# Flash_-_S25FL216K0PMFI041.net
KiCad netlist of a schematic drawn in Altium Designer
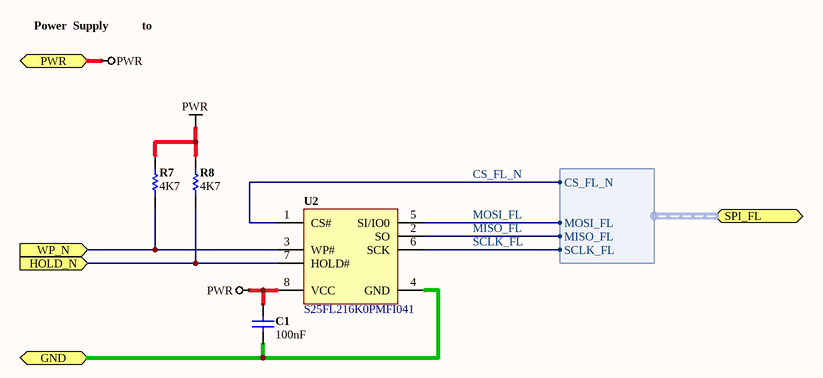
[diagram p0: Flash - S25FL216K0PMFI041.SchDoc]

(export (version "E")
  (design (tool "Eeschema 10.0.6"))
  (components
    (comp (ref "C1")
      (value "100nF")
      (footprint "CAPC0402(1005)60_L")
      (fields (field (name "TOLERANCE") "±10%") (field (name "Comment") "CAP 100nF 16V 0402(1005)"))
      (libsource (lib "Component_Database") (part "CAP_NP"))
    )
    (comp (ref "R7")
      (value "4K7")
      (footprint "RESC0402(1005)40_L")
      (fields (field (name "POWER") "1/16 W"))
      (libsource (lib "Component_Database") (part "RES"))
    )
    (comp (ref "R8")
      (value "4K7")
      (footprint "RESC0402(1005)40_L")
      (fields (field (name "POWER") "1/16 W"))
      (libsource (lib "Component_Database") (part "RES"))
    )
    (comp (ref "U2")
      (value "S25FL216K0PMFI041")
      (footprint "SPANSION-SOIC127P600X175-8M")
      (description "16-Mbit 3.0V Serial Flash Memory with Uniform 4 kB Sectors")
      (libsource (lib "S25FL216K0PMFI041") (part "S25FL216K0PMFI041"))
    )
  )
  (nets
    (net (code "2") (name "/CS_FL_N") (class "Default")
      (node (ref "U2") (pin "1") (pinfunction "CS#_1") (pintype "passive"))
    )
    (net (code "3") (name "/GND") (class "Default")
      (node (ref "C1") (pin "2") (pinfunction "2_2") (pintype "passive"))
      (node (ref "U2") (pin "4") (pinfunction "GND_4") (pintype "passive"))
    )
    (net (code "4") (name "/HOLD_N") (class "Default")
      (node (ref "R8") (pin "1") (pinfunction "1_1") (pintype "passive"))
      (node (ref "U2") (pin "7") (pinfunction "HOLD#_7") (pintype "passive"))
    )
    (net (code "5") (name "/MISO_FL") (class "Default")
      (node (ref "U2") (pin "2") (pinfunction "SO_2") (pintype "passive"))
    )
    (net (code "6") (name "/MOSI_FL") (class "Default")
      (node (ref "U2") (pin "5") (pinfunction "SI/IO0_5") (pintype "passive"))
    )
    (net (code "7") (name "/SCLK_FL") (class "Default")
      (node (ref "U2") (pin "6") (pinfunction "SCK_6") (pintype "passive"))
    )
    (net (code "8") (name "/WP_N") (class "Default")
      (node (ref "R7") (pin "1") (pinfunction "1_1") (pintype "passive"))
      (node (ref "U2") (pin "3") (pinfunction "WP#_3") (pintype "passive"))
    )
    (net (code "10") (name "PWR") (class "Default")
      (node (ref "C1") (pin "1") (pinfunction "1_1") (pintype "passive"))
      (node (ref "R7") (pin "2") (pinfunction "2_2") (pintype "passive"))
      (node (ref "R8") (pin "2") (pinfunction "2_2") (pintype "passive"))
      (node (ref "U2") (pin "8") (pinfunction "VCC_8") (pintype "passive"))
    )
  )
)
